# connectors.net
KiCad netlist of a schematic drawn in Altium Designer
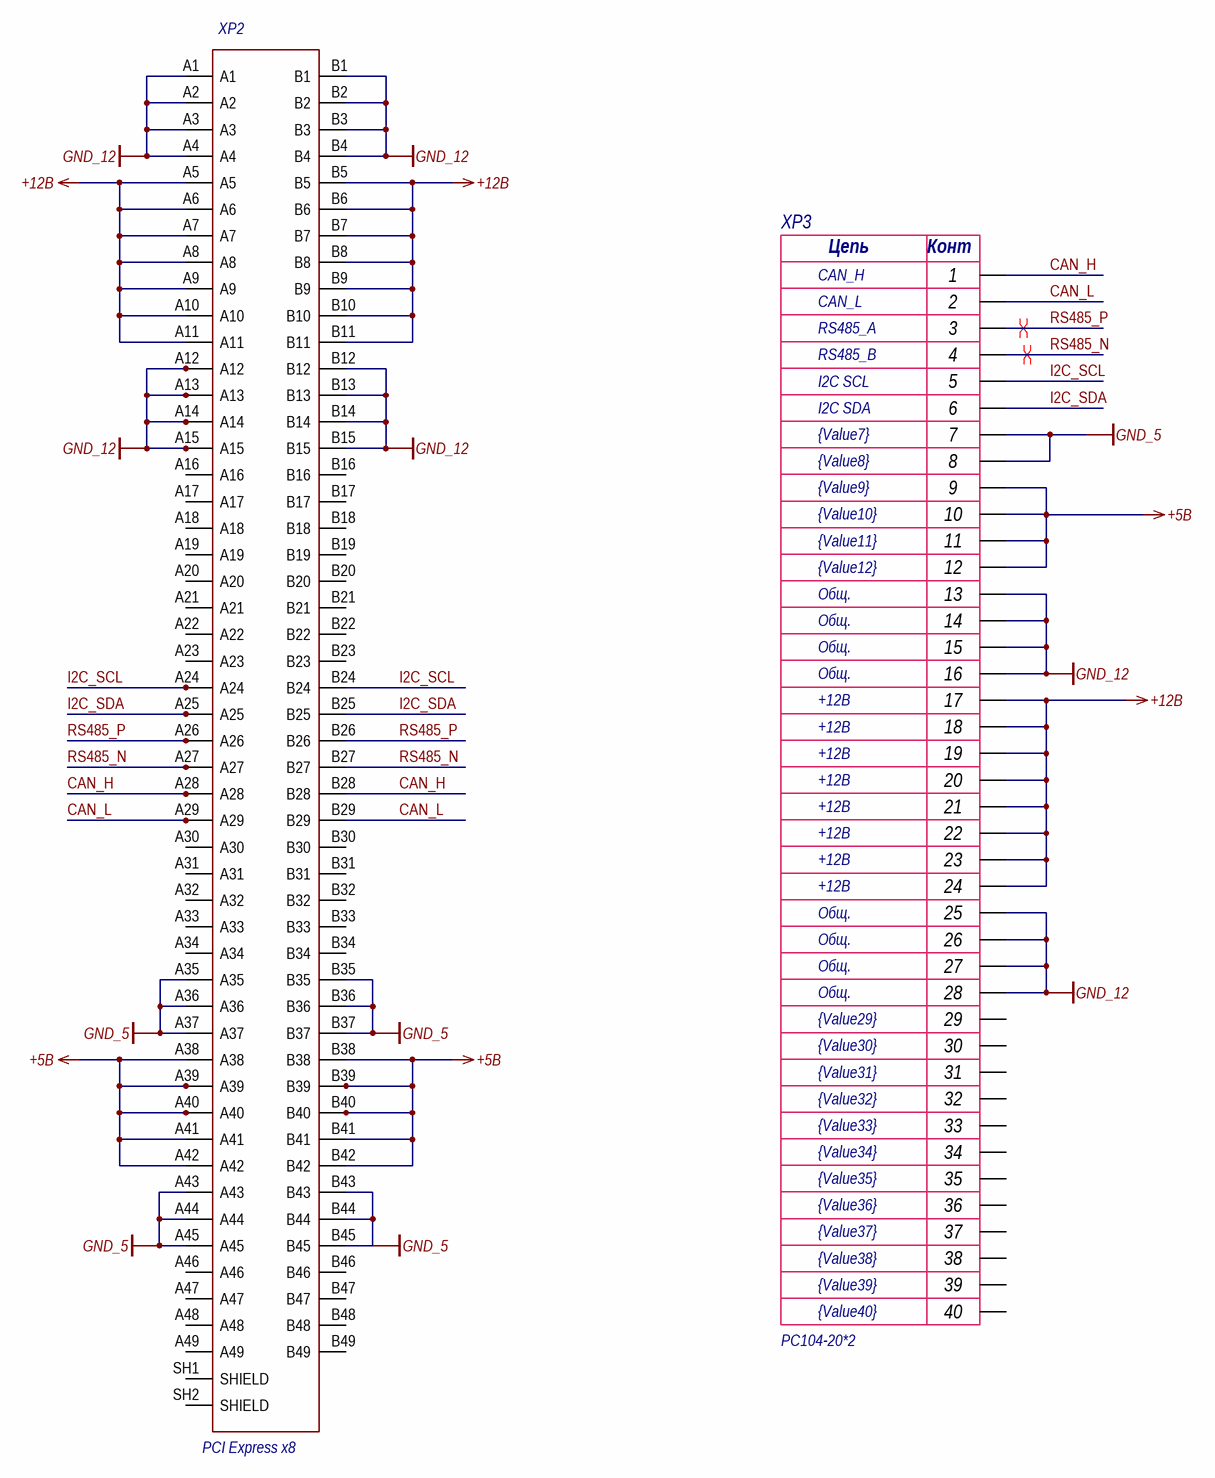
[diagram p0: connectors.SchDoc]

(export (version "E")
  (design (tool "Eeschema 10.0.6"))
  (components
    (comp (ref "XP2")
      (value "PCI Express x8")
      (footprint "pci-e-x8")
      (description "PCI ExpressÂ®x8 vertical Card Edge Connector, 98 Positions, 1mm (0.039inch) Pitch")
      (fields (field (name "MP") "10146070-112Y0LF") (field (name "MF") "Amphenol ICC (FCI)"))
      (libsource (lib "Hydrolib_sch") (part "PCI E x8"))
    )
    (comp (ref "XP3")
      (value "PC104-20*2")
      (footprint "PC - 104 20X2")
      (fields
        (field (name "VALUE10") "{Value10}")
        (field (name "VALUE11") "{Value11}")
        (field (name "VALUE12") "{Value12}")
        (field (name "VALUE13") "Общ.")
        (field (name "VALUE14") "Общ.")
        (field (name "VALUE15") "Общ.")
        (field (name "VALUE16") "Общ.")
        (field (name "VALUE17") "+12В")
        (field (name "VALUE18") "+12В")
        (field (name "VALUE1") "CAN_H")
        (field (name "VALUE2") "CAN_L")
        (field (name "VALUE3") "RS485_A")
        (field (name "VALUE4") "RS485_B")
        (field (name "VALUE5") "I2C SCL")
        (field (name "VALUE6") "I2C SDA")
        (field (name "VALUE7") "{Value7}")
        (field (name "VALUE8") "{Value8}")
        (field (name "VALUE9") "{Value9}")
        (field (name "VALUE19") "+12В")
        (field (name "VALUE20") "+12В")
        (field (name "VALUE21") "+12В")
        (field (name "VALUE22") "+12В")
        (field (name "VALUE23") "+12В")
        (field (name "VALUE24") "+12В")
        (field (name "VALUE25") "Общ.")
        (field (name "VALUE26") "Общ.")
        (field (name "VALUE27") "Общ.")
        (field (name "VALUE28") "Общ.")
        (field (name "VALUE29") "{Value29}")
        (field (name "VALUE30") "{Value30}")
        (field (name "VALUE31") "{Value31}")
        (field (name "VALUE32") "{Value32}")
        (field (name "VALUE33") "{Value33}")
        (field (name "VALUE34") "{Value34}")
        (field (name "VALUE35") "{Value35}")
        (field (name "VALUE36") "{Value36}")
        (field (name "VALUE37") "{Value37}")
        (field (name "VALUE38") "{Value38}")
        (field (name "VALUE39") "{Value39}")
        (field (name "VALUE40") "{Value40}")
      )
      (libsource (lib "Hydrolib_sch") (part "PC104-20*2"))
    )
  )
  (nets
    (net (code "1") (name "+5В") (class "Default")
      (node (ref "XP2") (pin "A38") (pinfunction "A38_A38") (pintype "passive"))
      (node (ref "XP2") (pin "A39") (pinfunction "A39_A39") (pintype "passive"))
      (node (ref "XP2") (pin "A40") (pinfunction "A40_A40") (pintype "passive"))
      (node (ref "XP2") (pin "A41") (pinfunction "A41_A41") (pintype "passive"))
      (node (ref "XP2") (pin "A42") (pinfunction "A42_A42") (pintype "passive"))
      (node (ref "XP2") (pin "B38") (pinfunction "B38_B38") (pintype "passive"))
      (node (ref "XP2") (pin "B39") (pinfunction "B39_B39") (pintype "passive"))
      (node (ref "XP2") (pin "B40") (pinfunction "B40_B40") (pintype "passive"))
      (node (ref "XP2") (pin "B41") (pinfunction "B41_B41") (pintype "passive"))
      (node (ref "XP2") (pin "B42") (pinfunction "B42_B42") (pintype "passive"))
      (node (ref "XP3") (pin "10") (pinfunction "10_10") (pintype "passive"))
      (node (ref "XP3") (pin "11") (pinfunction "11_11") (pintype "passive"))
      (node (ref "XP3") (pin "12") (pinfunction "12_12") (pintype "passive"))
      (node (ref "XP3") (pin "9") (pinfunction "9_9") (pintype "passive"))
    )
    (net (code "2") (name "+12В") (class "Default")
      (node (ref "XP2") (pin "A10") (pinfunction "A10_A10") (pintype "passive"))
      (node (ref "XP2") (pin "A11") (pinfunction "A11_A11") (pintype "passive"))
      (node (ref "XP2") (pin "A5") (pinfunction "A5_A5") (pintype "passive"))
      (node (ref "XP2") (pin "A6") (pinfunction "A6_A6") (pintype "passive"))
      (node (ref "XP2") (pin "A7") (pinfunction "A7_A7") (pintype "passive"))
      (node (ref "XP2") (pin "A8") (pinfunction "A8_A8") (pintype "passive"))
      (node (ref "XP2") (pin "A9") (pinfunction "A9_A9") (pintype "passive"))
      (node (ref "XP2") (pin "B10") (pinfunction "B10_B10") (pintype "passive"))
      (node (ref "XP2") (pin "B11") (pinfunction "B11_B11") (pintype "passive"))
      (node (ref "XP2") (pin "B5") (pinfunction "B5_B5") (pintype "passive"))
      (node (ref "XP2") (pin "B6") (pinfunction "B6_B6") (pintype "passive"))
      (node (ref "XP2") (pin "B7") (pinfunction "B7_B7") (pintype "passive"))
      (node (ref "XP2") (pin "B8") (pinfunction "B8_B8") (pintype "passive"))
      (node (ref "XP2") (pin "B9") (pinfunction "B9_B9") (pintype "passive"))
      (node (ref "XP3") (pin "17") (pinfunction "17_17") (pintype "passive"))
      (node (ref "XP3") (pin "18") (pinfunction "18_18") (pintype "passive"))
      (node (ref "XP3") (pin "19") (pinfunction "19_19") (pintype "passive"))
      (node (ref "XP3") (pin "20") (pinfunction "20_20") (pintype "passive"))
      (node (ref "XP3") (pin "21") (pinfunction "21_21") (pintype "passive"))
      (node (ref "XP3") (pin "22") (pinfunction "22_22") (pintype "passive"))
      (node (ref "XP3") (pin "23") (pinfunction "23_23") (pintype "passive"))
      (node (ref "XP3") (pin "24") (pinfunction "24_24") (pintype "passive"))
    )
    (net (code "3") (name "/CAN_H") (class "Default")
      (node (ref "XP2") (pin "A28") (pinfunction "A28_A28") (pintype "passive"))
      (node (ref "XP2") (pin "B28") (pinfunction "B28_B28") (pintype "passive"))
      (node (ref "XP3") (pin "1") (pinfunction "1_1") (pintype "passive"))
    )
    (net (code "4") (name "/CAN_L") (class "Default")
      (node (ref "XP2") (pin "A29") (pinfunction "A29_A29") (pintype "passive"))
      (node (ref "XP2") (pin "B29") (pinfunction "B29_B29") (pintype "passive"))
      (node (ref "XP3") (pin "2") (pinfunction "2_2") (pintype "passive"))
    )
    (net (code "5") (name "/I2C_SCL") (class "Default")
      (node (ref "XP2") (pin "A24") (pinfunction "A24_A24") (pintype "passive"))
      (node (ref "XP2") (pin "B24") (pinfunction "B24_B24") (pintype "passive"))
      (node (ref "XP3") (pin "5") (pinfunction "5_5") (pintype "passive"))
    )
    (net (code "6") (name "/I2C_SDA") (class "Default")
      (node (ref "XP2") (pin "A25") (pinfunction "A25_A25") (pintype "passive"))
      (node (ref "XP2") (pin "B25") (pinfunction "B25_B25") (pintype "passive"))
      (node (ref "XP3") (pin "6") (pinfunction "6_6") (pintype "passive"))
    )
    (net (code "7") (name "/RS485_N") (class "Default")
      (node (ref "XP2") (pin "A27") (pinfunction "A27_A27") (pintype "passive"))
      (node (ref "XP2") (pin "B27") (pinfunction "B27_B27") (pintype "passive"))
      (node (ref "XP3") (pin "4") (pinfunction "4_4") (pintype "passive"))
    )
    (net (code "8") (name "/RS485_P") (class "Default")
      (node (ref "XP2") (pin "A26") (pinfunction "A26_A26") (pintype "passive"))
      (node (ref "XP2") (pin "B26") (pinfunction "B26_B26") (pintype "passive"))
      (node (ref "XP3") (pin "3") (pinfunction "3_3") (pintype "passive"))
    )
    (net (code "9") (name "GND_5") (class "Default")
      (node (ref "XP2") (pin "A35") (pinfunction "A35_A35") (pintype "passive"))
      (node (ref "XP2") (pin "A36") (pinfunction "A36_A36") (pintype "passive"))
      (node (ref "XP2") (pin "A37") (pinfunction "A37_A37") (pintype "passive"))
      (node (ref "XP2") (pin "A43") (pinfunction "A43_A43") (pintype "passive"))
      (node (ref "XP2") (pin "A44") (pinfunction "A44_A44") (pintype "passive"))
      (node (ref "XP2") (pin "A45") (pinfunction "A45_A45") (pintype "passive"))
      (node (ref "XP2") (pin "B35") (pinfunction "B35_B35") (pintype "passive"))
      (node (ref "XP2") (pin "B36") (pinfunction "B36_B36") (pintype "passive"))
      (node (ref "XP2") (pin "B37") (pinfunction "B37_B37") (pintype "passive"))
      (node (ref "XP2") (pin "B43") (pinfunction "B43_B43") (pintype "passive"))
      (node (ref "XP2") (pin "B44") (pinfunction "B44_B44") (pintype "passive"))
      (node (ref "XP2") (pin "B45") (pinfunction "B45_B45") (pintype "passive"))
      (node (ref "XP3") (pin "7") (pinfunction "7_7") (pintype "passive"))
      (node (ref "XP3") (pin "8") (pinfunction "8_8") (pintype "passive"))
    )
    (net (code "10") (name "GND_12") (class "Default")
      (node (ref "XP2") (pin "A1") (pinfunction "A1_A1") (pintype "passive"))
      (node (ref "XP2") (pin "A12") (pinfunction "A12_A12") (pintype "passive"))
      (node (ref "XP2") (pin "A13") (pinfunction "A13_A13") (pintype "passive"))
      (node (ref "XP2") (pin "A14") (pinfunction "A14_A14") (pintype "passive"))
      (node (ref "XP2") (pin "A15") (pinfunction "A15_A15") (pintype "passive"))
      (node (ref "XP2") (pin "A2") (pinfunction "A2_A2") (pintype "passive"))
      (node (ref "XP2") (pin "A3") (pinfunction "A3_A3") (pintype "passive"))
      (node (ref "XP2") (pin "A4") (pinfunction "A4_A4") (pintype "passive"))
      (node (ref "XP2") (pin "B1") (pinfunction "B1_B1") (pintype "passive"))
      (node (ref "XP2") (pin "B12") (pinfunction "B12_B12") (pintype "passive"))
      (node (ref "XP2") (pin "B13") (pinfunction "B13_B13") (pintype "passive"))
      (node (ref "XP2") (pin "B14") (pinfunction "B14_B14") (pintype "passive"))
      (node (ref "XP2") (pin "B15") (pinfunction "B15_B15") (pintype "passive"))
      (node (ref "XP2") (pin "B2") (pinfunction "B2_B2") (pintype "passive"))
      (node (ref "XP2") (pin "B3") (pinfunction "B3_B3") (pintype "passive"))
      (node (ref "XP2") (pin "B4") (pinfunction "B4_B4") (pintype "passive"))
      (node (ref "XP3") (pin "13") (pinfunction "13_13") (pintype "passive"))
      (node (ref "XP3") (pin "14") (pinfunction "14_14") (pintype "passive"))
      (node (ref "XP3") (pin "15") (pinfunction "15_15") (pintype "passive"))
      (node (ref "XP3") (pin "16") (pinfunction "16_16") (pintype "passive"))
      (node (ref "XP3") (pin "25") (pinfunction "25_25") (pintype "passive"))
      (node (ref "XP3") (pin "26") (pinfunction "26_26") (pintype "passive"))
      (node (ref "XP3") (pin "27") (pinfunction "27_27") (pintype "passive"))
      (node (ref "XP3") (pin "28") (pinfunction "28_28") (pintype "passive"))
    )
    (net (code "11") (name "unconnected-(XP2-PadA16)") (class "Default")
      (node (ref "XP2") (pin "A16") (pinfunction "A16_A16") (pintype "passive"))
    )
    (net (code "12") (name "unconnected-(XP2-PadA17)") (class "Default")
      (node (ref "XP2") (pin "A17") (pinfunction "A17_A17") (pintype "passive"))
    )
    (net (code "13") (name "unconnected-(XP2-PadA18)") (class "Default")
      (node (ref "XP2") (pin "A18") (pinfunction "A18_A18") (pintype "passive"))
    )
    (net (code "14") (name "unconnected-(XP2-PadA19)") (class "Default")
      (node (ref "XP2") (pin "A19") (pinfunction "A19_A19") (pintype "passive"))
    )
    (net (code "15") (name "unconnected-(XP2-PadA20)") (class "Default")
      (node (ref "XP2") (pin "A20") (pinfunction "A20_A20") (pintype "passive"))
    )
    (net (code "16") (name "unconnected-(XP2-PadA21)") (class "Default")
      (node (ref "XP2") (pin "A21") (pinfunction "A21_A21") (pintype "passive"))
    )
    (net (code "17") (name "unconnected-(XP2-PadA22)") (class "Default")
      (node (ref "XP2") (pin "A22") (pinfunction "A22_A22") (pintype "passive"))
    )
    (net (code "18") (name "unconnected-(XP2-PadA23)") (class "Default")
      (node (ref "XP2") (pin "A23") (pinfunction "A23_A23") (pintype "passive"))
    )
    (net (code "19") (name "unconnected-(XP2-PadA30)") (class "Default")
      (node (ref "XP2") (pin "A30") (pinfunction "A30_A30") (pintype "passive"))
    )
    (net (code "20") (name "unconnected-(XP2-PadA31)") (class "Default")
      (node (ref "XP2") (pin "A31") (pinfunction "A31_A31") (pintype "passive"))
    )
    (net (code "21") (name "unconnected-(XP2-PadA32)") (class "Default")
      (node (ref "XP2") (pin "A32") (pinfunction "A32_A32") (pintype "passive"))
    )
    (net (code "22") (name "unconnected-(XP2-PadA33)") (class "Default")
      (node (ref "XP2") (pin "A33") (pinfunction "A33_A33") (pintype "passive"))
    )
    (net (code "23") (name "unconnected-(XP2-PadA34)") (class "Default")
      (node (ref "XP2") (pin "A34") (pinfunction "A34_A34") (pintype "passive"))
    )
    (net (code "24") (name "unconnected-(XP2-PadA46)") (class "Default")
      (node (ref "XP2") (pin "A46") (pinfunction "A46_A46") (pintype "passive"))
    )
    (net (code "25") (name "unconnected-(XP2-PadA47)") (class "Default")
      (node (ref "XP2") (pin "A47") (pinfunction "A47_A47") (pintype "passive"))
    )
    (net (code "26") (name "unconnected-(XP2-PadA48)") (class "Default")
      (node (ref "XP2") (pin "A48") (pinfunction "A48_A48") (pintype "passive"))
    )
    (net (code "27") (name "unconnected-(XP2-PadA49)") (class "Default")
      (node (ref "XP2") (pin "A49") (pinfunction "A49_A49") (pintype "passive"))
    )
    (net (code "28") (name "unconnected-(XP2-PadB16)") (class "Default")
      (node (ref "XP2") (pin "B16") (pinfunction "B16_B16") (pintype "passive"))
    )
    (net (code "29") (name "unconnected-(XP2-PadB17)") (class "Default")
      (node (ref "XP2") (pin "B17") (pinfunction "B17_B17") (pintype "passive"))
    )
    (net (code "30") (name "unconnected-(XP2-PadB18)") (class "Default")
      (node (ref "XP2") (pin "B18") (pinfunction "B18_B18") (pintype "passive"))
    )
    (net (code "31") (name "unconnected-(XP2-PadB19)") (class "Default")
      (node (ref "XP2") (pin "B19") (pinfunction "B19_B19") (pintype "passive"))
    )
    (net (code "32") (name "unconnected-(XP2-PadB20)") (class "Default")
      (node (ref "XP2") (pin "B20") (pinfunction "B20_B20") (pintype "passive"))
    )
    (net (code "33") (name "unconnected-(XP2-PadB21)") (class "Default")
      (node (ref "XP2") (pin "B21") (pinfunction "B21_B21") (pintype "passive"))
    )
    (net (code "34") (name "unconnected-(XP2-PadB22)") (class "Default")
      (node (ref "XP2") (pin "B22") (pinfunction "B22_B22") (pintype "passive"))
    )
    (net (code "35") (name "unconnected-(XP2-PadB23)") (class "Default")
      (node (ref "XP2") (pin "B23") (pinfunction "B23_B23") (pintype "passive"))
    )
    (net (code "36") (name "unconnected-(XP2-PadB30)") (class "Default")
      (node (ref "XP2") (pin "B30") (pinfunction "B30_B30") (pintype "passive"))
    )
    (net (code "37") (name "unconnected-(XP2-PadB31)") (class "Default")
      (node (ref "XP2") (pin "B31") (pinfunction "B31_B31") (pintype "passive"))
    )
    (net (code "38") (name "unconnected-(XP2-PadB32)") (class "Default")
      (node (ref "XP2") (pin "B32") (pinfunction "B32_B32") (pintype "passive"))
    )
    (net (code "39") (name "unconnected-(XP2-PadB33)") (class "Default")
      (node (ref "XP2") (pin "B33") (pinfunction "B33_B33") (pintype "passive"))
    )
    (net (code "40") (name "unconnected-(XP2-PadB34)") (class "Default")
      (node (ref "XP2") (pin "B34") (pinfunction "B34_B34") (pintype "passive"))
    )
    (net (code "41") (name "unconnected-(XP2-PadB46)") (class "Default")
      (node (ref "XP2") (pin "B46") (pinfunction "B46_B46") (pintype "passive"))
    )
    (net (code "42") (name "unconnected-(XP2-PadB47)") (class "Default")
      (node (ref "XP2") (pin "B47") (pinfunction "B47_B47") (pintype "passive"))
    )
    (net (code "43") (name "unconnected-(XP2-PadB48)") (class "Default")
      (node (ref "XP2") (pin "B48") (pinfunction "B48_B48") (pintype "passive"))
    )
    (net (code "44") (name "unconnected-(XP2-PadB49)") (class "Default")
      (node (ref "XP2") (pin "B49") (pinfunction "B49_B49") (pintype "passive"))
    )
    (net (code "45") (name "unconnected-(XP2-SHIELD-PadSH1)") (class "Default")
      (node (ref "XP2") (pin "SH1") (pinfunction "SHIELD_SH1") (pintype "passive"))
    )
    (net (code "46") (name "unconnected-(XP2-SHIELD-PadSH2)") (class "Default")
      (node (ref "XP2") (pin "SH2") (pinfunction "SHIELD_SH2") (pintype "passive"))
    )
    (net (code "47") (name "unconnected-(XP3-Pad29)") (class "Default")
      (node (ref "XP3") (pin "29") (pinfunction "29_29") (pintype "passive"))
    )
    (net (code "48") (name "unconnected-(XP3-Pad30)") (class "Default")
      (node (ref "XP3") (pin "30") (pinfunction "30_30") (pintype "passive"))
    )
    (net (code "49") (name "unconnected-(XP3-Pad31)") (class "Default")
      (node (ref "XP3") (pin "31") (pinfunction "31_31") (pintype "passive"))
    )
    (net (code "50") (name "unconnected-(XP3-Pad32)") (class "Default")
      (node (ref "XP3") (pin "32") (pinfunction "32_32") (pintype "passive"))
    )
    (net (code "51") (name "unconnected-(XP3-Pad33)") (class "Default")
      (node (ref "XP3") (pin "33") (pinfunction "33_33") (pintype "passive"))
    )
    (net (code "52") (name "unconnected-(XP3-Pad34)") (class "Default")
      (node (ref "XP3") (pin "34") (pinfunction "34_34") (pintype "passive"))
    )
    (net (code "53") (name "unconnected-(XP3-Pad35)") (class "Default")
      (node (ref "XP3") (pin "35") (pinfunction "35_35") (pintype "passive"))
    )
    (net (code "54") (name "unconnected-(XP3-Pad36)") (class "Default")
      (node (ref "XP3") (pin "36") (pinfunction "36_36") (pintype "passive"))
    )
    (net (code "55") (name "unconnected-(XP3-Pad37)") (class "Default")
      (node (ref "XP3") (pin "37") (pinfunction "37_37") (pintype "passive"))
    )
    (net (code "56") (name "unconnected-(XP3-Pad38)") (class "Default")
      (node (ref "XP3") (pin "38") (pinfunction "38_38") (pintype "passive"))
    )
    (net (code "57") (name "unconnected-(XP3-Pad39)") (class "Default")
      (node (ref "XP3") (pin "39") (pinfunction "39_39") (pintype "passive"))
    )
    (net (code "58") (name "unconnected-(XP3-Pad40)") (class "Default")
      (node (ref "XP3") (pin "40") (pinfunction "40_40") (pintype "passive"))
    )
  )
)
